# Mako_DSP_Memory_R2_0.net
KiCad netlist of a schematic drawn in Altium Designer
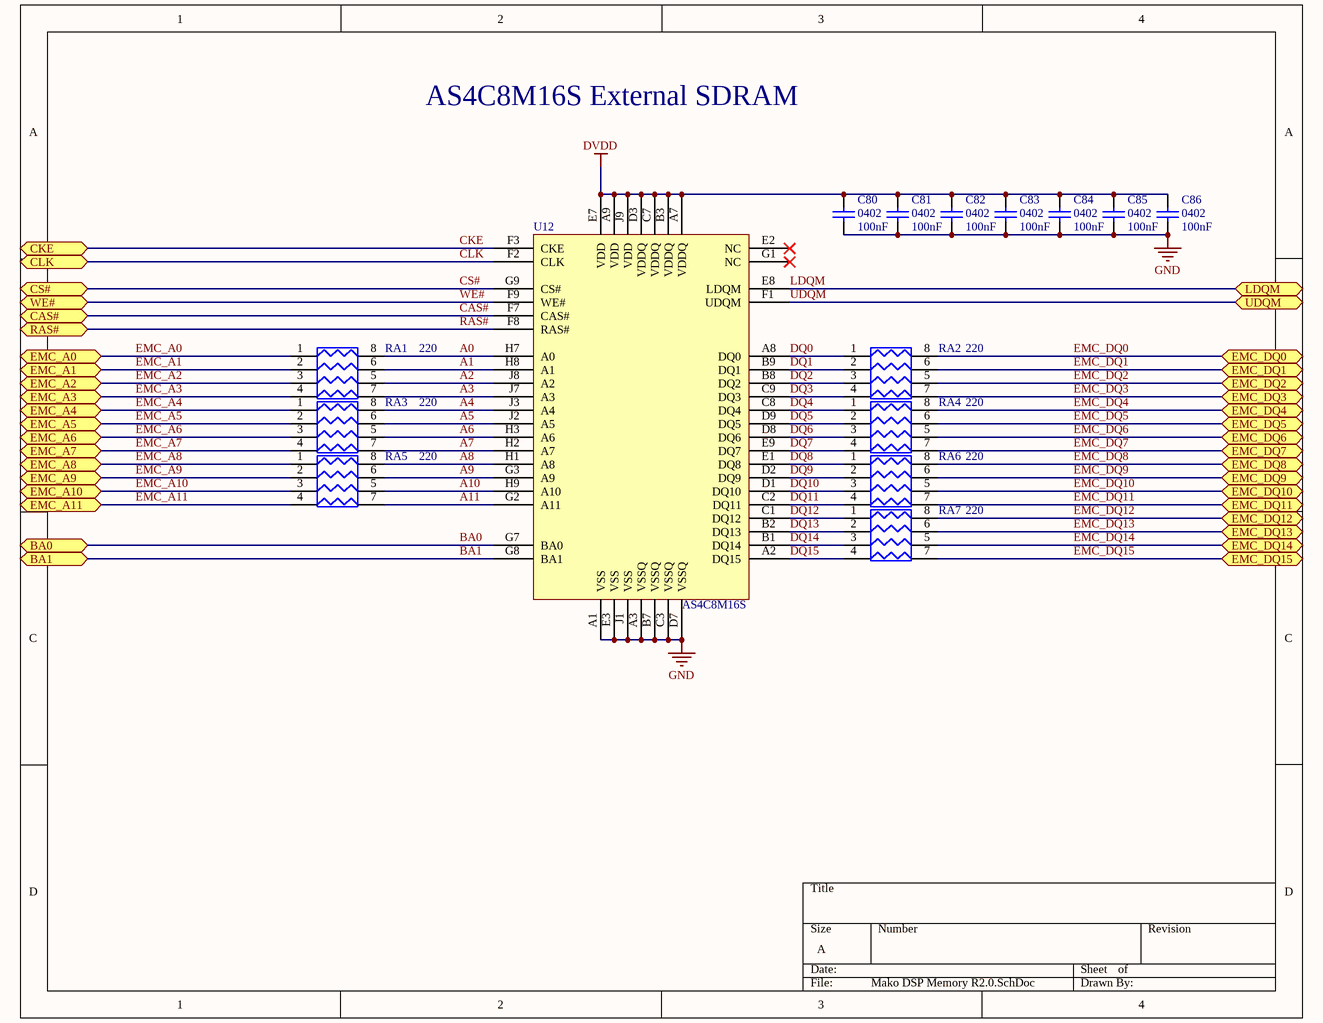
[diagram p0: Mako DSP Memory R2.0.SchDoc]

(export (version "E")
  (design (tool "Eeschema 10.0.6"))
  (components
    (comp (ref "C80")
      (value "0402")
      (footprint "0402")
      (description "Capacitor (Semiconductor SIM Model)")
      (fields (field (name "ALTIUM_VALUE") "100nF") (field (name "PUBLISHER") "Altium Limited"))
      (libsource (lib "Miscellaneous Devices") (part "Cap Semi"))
    )
    (comp (ref "C81")
      (value "0402")
      (footprint "0402")
      (description "Capacitor (Semiconductor SIM Model)")
      (fields (field (name "ALTIUM_VALUE") "100nF") (field (name "PUBLISHER") "Altium Limited"))
      (libsource (lib "Miscellaneous Devices") (part "Cap Semi"))
    )
    (comp (ref "C82")
      (value "0402")
      (footprint "0402")
      (description "Capacitor (Semiconductor SIM Model)")
      (fields (field (name "ALTIUM_VALUE") "100nF") (field (name "PUBLISHER") "Altium Limited"))
      (libsource (lib "Miscellaneous Devices") (part "Cap Semi"))
    )
    (comp (ref "C83")
      (value "0402")
      (footprint "0402")
      (description "Capacitor (Semiconductor SIM Model)")
      (fields (field (name "ALTIUM_VALUE") "100nF") (field (name "PUBLISHER") "Altium Limited"))
      (libsource (lib "Miscellaneous Devices") (part "Cap Semi"))
    )
    (comp (ref "C84")
      (value "0402")
      (footprint "0402")
      (description "Capacitor (Semiconductor SIM Model)")
      (fields (field (name "ALTIUM_VALUE") "100nF") (field (name "PUBLISHER") "Altium Limited"))
      (libsource (lib "Miscellaneous Devices") (part "Cap Semi"))
    )
    (comp (ref "C85")
      (value "0402")
      (footprint "0402")
      (description "Capacitor (Semiconductor SIM Model)")
      (fields (field (name "ALTIUM_VALUE") "100nF") (field (name "PUBLISHER") "Altium Limited"))
      (libsource (lib "Miscellaneous Devices") (part "Cap Semi"))
    )
    (comp (ref "C86")
      (value "0402")
      (footprint "0402")
      (description "Capacitor (Semiconductor SIM Model)")
      (fields (field (name "ALTIUM_VALUE") "100nF") (field (name "PUBLISHER") "Altium Limited"))
      (libsource (lib "Miscellaneous Devices") (part "Cap Semi"))
    )
    (comp (ref "RA1")
      (value "220")
      (footprint "742C083")
      (description "Resistor array")
      (fields (field (name "Comment") "RESISTOR ARRAY"))
      (libsource (lib "Mako DSP Schematic Library") (part "RESISTOR ARRAY"))
    )
    (comp (ref "RA2")
      (value "220")
      (footprint "742C083")
      (description "Resistor array")
      (fields (field (name "Comment") "RESISTOR ARRAY"))
      (libsource (lib "Mako DSP Schematic Library") (part "RESISTOR ARRAY"))
    )
    (comp (ref "RA3")
      (value "220")
      (footprint "742C083")
      (description "Resistor array")
      (fields (field (name "Comment") "RESISTOR ARRAY"))
      (libsource (lib "Mako DSP Schematic Library") (part "RESISTOR ARRAY"))
    )
    (comp (ref "RA4")
      (value "220")
      (footprint "742C083")
      (description "Resistor array")
      (fields (field (name "Comment") "RESISTOR ARRAY"))
      (libsource (lib "Mako DSP Schematic Library") (part "RESISTOR ARRAY"))
    )
    (comp (ref "RA5")
      (value "220")
      (footprint "742C083")
      (description "Resistor array")
      (fields (field (name "Comment") "RESISTOR ARRAY"))
      (libsource (lib "Mako DSP Schematic Library") (part "RESISTOR ARRAY"))
    )
    (comp (ref "RA6")
      (value "220")
      (footprint "742C083")
      (description "Resistor array")
      (fields (field (name "Comment") "RESISTOR ARRAY"))
      (libsource (lib "Mako DSP Schematic Library") (part "RESISTOR ARRAY"))
    )
    (comp (ref "RA7")
      (value "220")
      (footprint "742C083")
      (description "Resistor array")
      (fields (field (name "Comment") "RESISTOR ARRAY"))
      (libsource (lib "Mako DSP Schematic Library") (part "RESISTOR ARRAY"))
    )
    (comp (ref "U12")
      (value "AS4C8M16S")
      (footprint "AS4C8M16S")
      (libsource (lib "Mako DSP Schematic Library") (part "AS4C8M16S"))
    )
  )
  (nets
    (net (code "1") (name "/A0") (class "Default")
      (node (ref "RA1") (pin "8") (pinfunction "8_8") (pintype "passive"))
      (node (ref "U12") (pin "H7") (pinfunction "A0_H7") (pintype "passive"))
    )
    (net (code "2") (name "/A1") (class "Default")
      (node (ref "RA1") (pin "6") (pinfunction "6_6") (pintype "passive"))
      (node (ref "U12") (pin "H8") (pinfunction "A1_H8") (pintype "passive"))
    )
    (net (code "3") (name "/A2") (class "Default")
      (node (ref "RA1") (pin "5") (pinfunction "5_5") (pintype "passive"))
      (node (ref "U12") (pin "J8") (pinfunction "A2_J8") (pintype "passive"))
    )
    (net (code "4") (name "/A3") (class "Default")
      (node (ref "RA1") (pin "7") (pinfunction "7_7") (pintype "passive"))
      (node (ref "U12") (pin "J7") (pinfunction "A3_J7") (pintype "passive"))
    )
    (net (code "5") (name "/A4") (class "Default")
      (node (ref "RA3") (pin "8") (pinfunction "8_8") (pintype "passive"))
      (node (ref "U12") (pin "J3") (pinfunction "A4_J3") (pintype "passive"))
    )
    (net (code "6") (name "/A5") (class "Default")
      (node (ref "RA3") (pin "6") (pinfunction "6_6") (pintype "passive"))
      (node (ref "U12") (pin "J2") (pinfunction "A5_J2") (pintype "passive"))
    )
    (net (code "7") (name "/A6") (class "Default")
      (node (ref "RA3") (pin "5") (pinfunction "5_5") (pintype "passive"))
      (node (ref "U12") (pin "H3") (pinfunction "A6_H3") (pintype "passive"))
    )
    (net (code "8") (name "/A7") (class "Default")
      (node (ref "RA3") (pin "7") (pinfunction "7_7") (pintype "passive"))
      (node (ref "U12") (pin "H2") (pinfunction "A7_H2") (pintype "passive"))
    )
    (net (code "9") (name "/A8") (class "Default")
      (node (ref "RA5") (pin "8") (pinfunction "8_8") (pintype "passive"))
      (node (ref "U12") (pin "H1") (pinfunction "A8_H1") (pintype "passive"))
    )
    (net (code "10") (name "/A9") (class "Default")
      (node (ref "RA5") (pin "6") (pinfunction "6_6") (pintype "passive"))
      (node (ref "U12") (pin "G3") (pinfunction "A9_G3") (pintype "passive"))
    )
    (net (code "11") (name "/A10") (class "Default")
      (node (ref "RA5") (pin "5") (pinfunction "5_5") (pintype "passive"))
      (node (ref "U12") (pin "H9") (pinfunction "A10_H9") (pintype "passive"))
    )
    (net (code "12") (name "/A11") (class "Default")
      (node (ref "RA5") (pin "7") (pinfunction "7_7") (pintype "passive"))
      (node (ref "U12") (pin "G2") (pinfunction "A11_G2") (pintype "passive"))
    )
    (net (code "13") (name "/BA0") (class "Default")
      (node (ref "U12") (pin "G7") (pinfunction "BA0_G7") (pintype "passive"))
    )
    (net (code "14") (name "/BA1") (class "Default")
      (node (ref "U12") (pin "G8") (pinfunction "BA1_G8") (pintype "passive"))
    )
    (net (code "15") (name "/CAS#") (class "Default")
      (node (ref "U12") (pin "F7") (pinfunction "CAS#_F7") (pintype "passive"))
    )
    (net (code "16") (name "/CKE") (class "Default")
      (node (ref "U12") (pin "F3") (pinfunction "CKE_F3") (pintype "passive"))
    )
    (net (code "17") (name "/CLK") (class "Default")
      (node (ref "U12") (pin "F2") (pinfunction "CLK_F2") (pintype "passive"))
    )
    (net (code "18") (name "/CS#") (class "Default")
      (node (ref "U12") (pin "G9") (pinfunction "CS#_G9") (pintype "passive"))
    )
    (net (code "19") (name "/DQ0") (class "Default")
      (node (ref "RA2") (pin "1") (pinfunction "1_1") (pintype "passive"))
      (node (ref "U12") (pin "A8") (pinfunction "DQ0_A8") (pintype "passive"))
    )
    (net (code "20") (name "/DQ1") (class "Default")
      (node (ref "RA2") (pin "2") (pinfunction "2_2") (pintype "passive"))
      (node (ref "U12") (pin "B9") (pinfunction "DQ1_B9") (pintype "passive"))
    )
    (net (code "21") (name "/DQ2") (class "Default")
      (node (ref "RA2") (pin "3") (pinfunction "3_3") (pintype "passive"))
      (node (ref "U12") (pin "B8") (pinfunction "DQ2_B8") (pintype "passive"))
    )
    (net (code "22") (name "/DQ3") (class "Default")
      (node (ref "RA2") (pin "4") (pinfunction "4_4") (pintype "passive"))
      (node (ref "U12") (pin "C9") (pinfunction "DQ3_C9") (pintype "passive"))
    )
    (net (code "23") (name "/DQ4") (class "Default")
      (node (ref "RA4") (pin "1") (pinfunction "1_1") (pintype "passive"))
      (node (ref "U12") (pin "C8") (pinfunction "DQ4_C8") (pintype "passive"))
    )
    (net (code "24") (name "/DQ5") (class "Default")
      (node (ref "RA4") (pin "2") (pinfunction "2_2") (pintype "passive"))
      (node (ref "U12") (pin "D9") (pinfunction "DQ5_D9") (pintype "passive"))
    )
    (net (code "25") (name "/DQ6") (class "Default")
      (node (ref "RA4") (pin "3") (pinfunction "3_3") (pintype "passive"))
      (node (ref "U12") (pin "D8") (pinfunction "DQ6_D8") (pintype "passive"))
    )
    (net (code "26") (name "/DQ7") (class "Default")
      (node (ref "RA4") (pin "4") (pinfunction "4_4") (pintype "passive"))
      (node (ref "U12") (pin "E9") (pinfunction "DQ7_E9") (pintype "passive"))
    )
    (net (code "27") (name "/DQ8") (class "Default")
      (node (ref "RA6") (pin "1") (pinfunction "1_1") (pintype "passive"))
      (node (ref "U12") (pin "E1") (pinfunction "DQ8_E1") (pintype "passive"))
    )
    (net (code "28") (name "/DQ9") (class "Default")
      (node (ref "RA6") (pin "2") (pinfunction "2_2") (pintype "passive"))
      (node (ref "U12") (pin "D2") (pinfunction "DQ9_D2") (pintype "passive"))
    )
    (net (code "29") (name "/DQ10") (class "Default")
      (node (ref "RA6") (pin "3") (pinfunction "3_3") (pintype "passive"))
      (node (ref "U12") (pin "D1") (pinfunction "DQ10_D1") (pintype "passive"))
    )
    (net (code "30") (name "/DQ11") (class "Default")
      (node (ref "RA6") (pin "4") (pinfunction "4_4") (pintype "passive"))
      (node (ref "U12") (pin "C2") (pinfunction "DQ11_C2") (pintype "passive"))
    )
    (net (code "31") (name "/DQ12") (class "Default")
      (node (ref "RA7") (pin "1") (pinfunction "1_1") (pintype "passive"))
      (node (ref "U12") (pin "C1") (pinfunction "DQ12_C1") (pintype "passive"))
    )
    (net (code "32") (name "/DQ13") (class "Default")
      (node (ref "RA7") (pin "2") (pinfunction "2_2") (pintype "passive"))
      (node (ref "U12") (pin "B2") (pinfunction "DQ13_B2") (pintype "passive"))
    )
    (net (code "33") (name "/DQ14") (class "Default")
      (node (ref "RA7") (pin "3") (pinfunction "3_3") (pintype "passive"))
      (node (ref "U12") (pin "B1") (pinfunction "DQ14_B1") (pintype "passive"))
    )
    (net (code "34") (name "/DQ15") (class "Default")
      (node (ref "RA7") (pin "4") (pinfunction "4_4") (pintype "passive"))
      (node (ref "U12") (pin "A2") (pinfunction "DQ15_A2") (pintype "passive"))
    )
    (net (code "35") (name "/EMC_A0") (class "Default")
      (node (ref "RA1") (pin "1") (pinfunction "1_1") (pintype "passive"))
    )
    (net (code "36") (name "/EMC_A1") (class "Default")
      (node (ref "RA1") (pin "2") (pinfunction "2_2") (pintype "passive"))
    )
    (net (code "37") (name "/EMC_A2") (class "Default")
      (node (ref "RA1") (pin "3") (pinfunction "3_3") (pintype "passive"))
    )
    (net (code "38") (name "/EMC_A3") (class "Default")
      (node (ref "RA1") (pin "4") (pinfunction "4_4") (pintype "passive"))
    )
    (net (code "39") (name "/EMC_A4") (class "Default")
      (node (ref "RA3") (pin "1") (pinfunction "1_1") (pintype "passive"))
    )
    (net (code "40") (name "/EMC_A5") (class "Default")
      (node (ref "RA3") (pin "2") (pinfunction "2_2") (pintype "passive"))
    )
    (net (code "41") (name "/EMC_A6") (class "Default")
      (node (ref "RA3") (pin "3") (pinfunction "3_3") (pintype "passive"))
    )
    (net (code "42") (name "/EMC_A7") (class "Default")
      (node (ref "RA3") (pin "4") (pinfunction "4_4") (pintype "passive"))
    )
    (net (code "43") (name "/EMC_A8") (class "Default")
      (node (ref "RA5") (pin "1") (pinfunction "1_1") (pintype "passive"))
    )
    (net (code "44") (name "/EMC_A9") (class "Default")
      (node (ref "RA5") (pin "2") (pinfunction "2_2") (pintype "passive"))
    )
    (net (code "45") (name "/EMC_A10") (class "Default")
      (node (ref "RA5") (pin "3") (pinfunction "3_3") (pintype "passive"))
    )
    (net (code "46") (name "/EMC_A11") (class "Default")
      (node (ref "RA5") (pin "4") (pinfunction "4_4") (pintype "passive"))
    )
    (net (code "47") (name "/EMC_DQ0") (class "Default")
      (node (ref "RA2") (pin "8") (pinfunction "8_8") (pintype "passive"))
    )
    (net (code "48") (name "/EMC_DQ1") (class "Default")
      (node (ref "RA2") (pin "6") (pinfunction "6_6") (pintype "passive"))
    )
    (net (code "49") (name "/EMC_DQ2") (class "Default")
      (node (ref "RA2") (pin "5") (pinfunction "5_5") (pintype "passive"))
    )
    (net (code "50") (name "/EMC_DQ3") (class "Default")
      (node (ref "RA2") (pin "7") (pinfunction "7_7") (pintype "passive"))
    )
    (net (code "51") (name "/EMC_DQ4") (class "Default")
      (node (ref "RA4") (pin "8") (pinfunction "8_8") (pintype "passive"))
    )
    (net (code "52") (name "/EMC_DQ5") (class "Default")
      (node (ref "RA4") (pin "6") (pinfunction "6_6") (pintype "passive"))
    )
    (net (code "53") (name "/EMC_DQ6") (class "Default")
      (node (ref "RA4") (pin "5") (pinfunction "5_5") (pintype "passive"))
    )
    (net (code "54") (name "/EMC_DQ7") (class "Default")
      (node (ref "RA4") (pin "7") (pinfunction "7_7") (pintype "passive"))
    )
    (net (code "55") (name "/EMC_DQ8") (class "Default")
      (node (ref "RA6") (pin "8") (pinfunction "8_8") (pintype "passive"))
    )
    (net (code "56") (name "/EMC_DQ9") (class "Default")
      (node (ref "RA6") (pin "6") (pinfunction "6_6") (pintype "passive"))
    )
    (net (code "57") (name "/EMC_DQ10") (class "Default")
      (node (ref "RA6") (pin "5") (pinfunction "5_5") (pintype "passive"))
    )
    (net (code "58") (name "/EMC_DQ11") (class "Default")
      (node (ref "RA6") (pin "7") (pinfunction "7_7") (pintype "passive"))
    )
    (net (code "59") (name "/EMC_DQ12") (class "Default")
      (node (ref "RA7") (pin "8") (pinfunction "8_8") (pintype "passive"))
    )
    (net (code "60") (name "/EMC_DQ13") (class "Default")
      (node (ref "RA7") (pin "6") (pinfunction "6_6") (pintype "passive"))
    )
    (net (code "61") (name "/EMC_DQ14") (class "Default")
      (node (ref "RA7") (pin "5") (pinfunction "5_5") (pintype "passive"))
    )
    (net (code "62") (name "/EMC_DQ15") (class "Default")
      (node (ref "RA7") (pin "7") (pinfunction "7_7") (pintype "passive"))
    )
    (net (code "63") (name "/LDQM") (class "Default")
      (node (ref "U12") (pin "E8") (pinfunction "LDQM_E8") (pintype "passive"))
    )
    (net (code "64") (name "/RAS#") (class "Default")
      (node (ref "U12") (pin "F8") (pinfunction "RAS#_F8") (pintype "passive"))
    )
    (net (code "65") (name "/UDQM") (class "Default")
      (node (ref "U12") (pin "F1") (pinfunction "UDQM_F1") (pintype "passive"))
    )
    (net (code "66") (name "/WE#") (class "Default")
      (node (ref "U12") (pin "F9") (pinfunction "WE#_F9") (pintype "passive"))
    )
    (net (code "67") (name "DVDD") (class "Default")
      (node (ref "C80") (pin "2") (pinfunction "2_2") (pintype "passive"))
      (node (ref "C81") (pin "2") (pinfunction "2_2") (pintype "passive"))
      (node (ref "C82") (pin "2") (pinfunction "2_2") (pintype "passive"))
      (node (ref "C83") (pin "2") (pinfunction "2_2") (pintype "passive"))
      (node (ref "C84") (pin "2") (pinfunction "2_2") (pintype "passive"))
      (node (ref "C85") (pin "2") (pinfunction "2_2") (pintype "passive"))
      (node (ref "C86") (pin "2") (pinfunction "2_2") (pintype "passive"))
      (node (ref "U12") (pin "A7") (pinfunction "VDDQ_A7") (pintype "passive"))
      (node (ref "U12") (pin "A9") (pinfunction "VDD_A9") (pintype "passive"))
      (node (ref "U12") (pin "B3") (pinfunction "VDDQ_B3") (pintype "passive"))
      (node (ref "U12") (pin "C7") (pinfunction "VDDQ_C7") (pintype "passive"))
      (node (ref "U12") (pin "D3") (pinfunction "VDDQ_D3") (pintype "passive"))
      (node (ref "U12") (pin "E7") (pinfunction "VDD_E7") (pintype "passive"))
      (node (ref "U12") (pin "J9") (pinfunction "VDD_J9") (pintype "passive"))
    )
    (net (code "68") (name "GND") (class "Default")
      (node (ref "C80") (pin "1") (pinfunction "1_1") (pintype "passive"))
      (node (ref "C81") (pin "1") (pinfunction "1_1") (pintype "passive"))
      (node (ref "C82") (pin "1") (pinfunction "1_1") (pintype "passive"))
      (node (ref "C83") (pin "1") (pinfunction "1_1") (pintype "passive"))
      (node (ref "C84") (pin "1") (pinfunction "1_1") (pintype "passive"))
      (node (ref "C85") (pin "1") (pinfunction "1_1") (pintype "passive"))
      (node (ref "C86") (pin "1") (pinfunction "1_1") (pintype "passive"))
      (node (ref "U12") (pin "A1") (pinfunction "VSS_A1") (pintype "passive"))
      (node (ref "U12") (pin "A3") (pinfunction "VSSQ_A3") (pintype "passive"))
      (node (ref "U12") (pin "B7") (pinfunction "VSSQ_B7") (pintype "passive"))
      (node (ref "U12") (pin "C3") (pinfunction "VSSQ_C3") (pintype "passive"))
      (node (ref "U12") (pin "D7") (pinfunction "VSSQ_D7") (pintype "passive"))
      (node (ref "U12") (pin "E3") (pinfunction "VSS_E3") (pintype "passive"))
      (node (ref "U12") (pin "J1") (pinfunction "VSS_J1") (pintype "passive"))
    )
    (net (code "69") (name "unconnected-(U12-NC-PadE2)") (class "Default")
      (node (ref "U12") (pin "E2") (pinfunction "NC_E2") (pintype "passive+no_connect"))
    )
    (net (code "70") (name "unconnected-(U12-NC-PadG1)") (class "Default")
      (node (ref "U12") (pin "G1") (pinfunction "NC_G1") (pintype "passive+no_connect"))
    )
  )
)
